# TubeScreamer.net
KiCad netlist of a schematic drawn in EAGLE
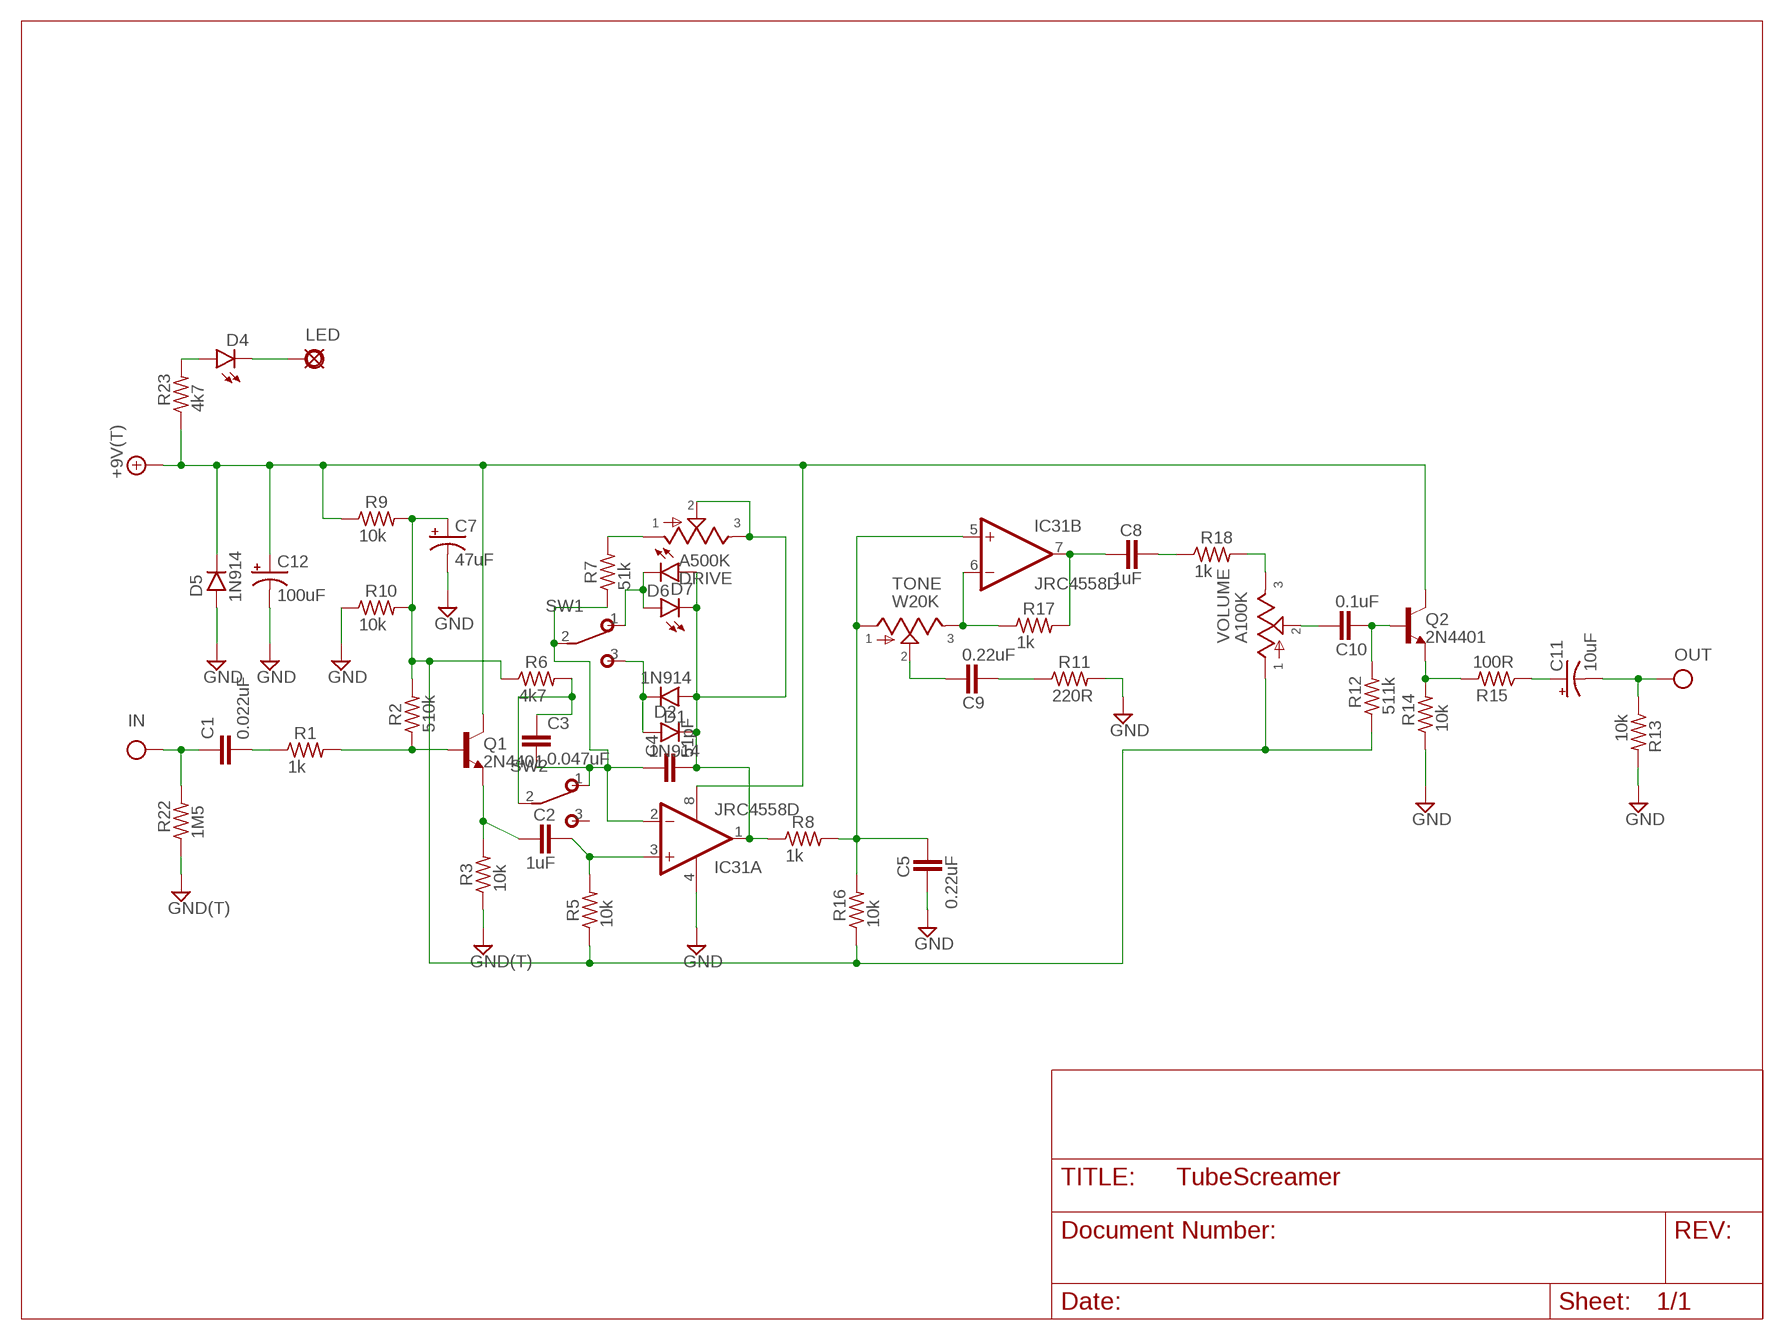
[diagram p0: schematic, sheet 1]

(export (version "E")
  (design (tool "Eeschema 10.0.6"))
  (components
    (comp (ref "+9V")
      (value "+9V(T)")
      (footprint "eagle-import:SQUARE")
      (libsource (lib "eagle-import") (part "+9V(T)"))
    )
    (comp (ref "C1")
      (value "0.022uF")
      (footprint "eagle-import:070X030")
      (libsource (lib "eagle-import") (part "070X0302"))
    )
    (comp (ref "C2")
      (value "1uF")
      (footprint "eagle-import:072X035")
      (libsource (lib "eagle-import") (part "072X0352"))
    )
    (comp (ref "C3")
      (value "0.047uF")
      (footprint "eagle-import:070X030")
      (libsource (lib "eagle-import") (part "070X0302"))
    )
    (comp (ref "C4")
      (value "51pF")
      (footprint "eagle-import:050X030_025")
      (libsource (lib "eagle-import") (part "050X030_0251"))
    )
    (comp (ref "C5")
      (value "0.22uF")
      (footprint "eagle-import:072X035")
      (libsource (lib "eagle-import") (part "072X0352"))
    )
    (comp (ref "C7")
      (value "47uF")
      (footprint "eagle-import:063_025")
      (libsource (lib "eagle-import") (part "0631"))
    )
    (comp (ref "C8")
      (value "1uF")
      (footprint "eagle-import:072X035")
      (libsource (lib "eagle-import") (part "072X0352"))
    )
    (comp (ref "C9")
      (value "0.22uF")
      (footprint "eagle-import:072X035")
      (libsource (lib "eagle-import") (part "072X0352"))
    )
    (comp (ref "C10")
      (value "0.1uF")
      (footprint "eagle-import:072X035")
      (libsource (lib "eagle-import") (part "072X0352"))
    )
    (comp (ref "C11")
      (value "10uF")
      (footprint "eagle-import:063_025")
      (libsource (lib "eagle-import") (part "0631"))
    )
    (comp (ref "C12")
      (value "100uF")
      (footprint "eagle-import:080_035")
      (libsource (lib "eagle-import") (part "080"))
    )
    (comp (ref "D1")
      (value "1N914")
      (footprint "eagle-import:DO35-3")
      (libsource (lib "eagle-import") (part "1N914.3"))
    )
    (comp (ref "D2")
      (value "1N914")
      (footprint "eagle-import:DO35-3")
      (libsource (lib "eagle-import") (part "1N914.3"))
    )
    (comp (ref "D4")
      (value "LED3MM")
      (footprint "eagle-import:LED3MM")
      (libsource (lib "eagle-import") (part "LED3MM"))
    )
    (comp (ref "D5")
      (value "1N914")
      (footprint "eagle-import:DO35-3")
      (libsource (lib "eagle-import") (part "1N914.3"))
    )
    (comp (ref "D6")
      (value "LED3MM")
      (footprint "eagle-import:LED3MM")
      (libsource (lib "eagle-import") (part "LED3MM"))
    )
    (comp (ref "D7")
      (value "LED3MM")
      (footprint "eagle-import:LED3MM")
      (libsource (lib "eagle-import") (part "LED3MM"))
    )
    (comp (ref "DRIVE")
      (value "A500K")
      (footprint "eagle-import:16MM")
      (libsource (lib "eagle-import") (part "POT16MM"))
    )
    (comp (ref "GD2")
      (value "GND(T)")
      (footprint "eagle-import:SQUARE")
      (libsource (lib "eagle-import") (part "GND(T)"))
    )
    (comp (ref "GND")
      (value "GND(T)")
      (footprint "eagle-import:SQUARE")
      (libsource (lib "eagle-import") (part "GND(T)"))
    )
    (comp (ref "IC31")
      (value "JRC4558D")
      (footprint "eagle-import:DIL08")
      (libsource (lib "eagle-import") (part "4558NLM"))
    )
    (comp (ref "IN")
      (value "IN(T)")
      (footprint "eagle-import:SQUARE")
      (libsource (lib "eagle-import") (part "IN(T)"))
    )
    (comp (ref "LED")
      (value "3mm")
      (footprint "eagle-import:SQUARE")
      (libsource (lib "eagle-import") (part "PAD"))
    )
    (comp (ref "OUT")
      (value "OUT(T)")
      (footprint "eagle-import:SQUARE")
      (libsource (lib "eagle-import") (part "OUT(T)"))
    )
    (comp (ref "Q1")
      (value "2N4401")
      (footprint "eagle-import:TO92-")
      (libsource (lib "eagle-import") (part "2N3904"))
    )
    (comp (ref "Q2")
      (value "2N4401")
      (footprint "eagle-import:TO92-")
      (libsource (lib "eagle-import") (part "2N3904"))
    )
    (comp (ref "R1")
      (value "1k")
      (footprint "eagle-import:R0207_3")
      (libsource (lib "eagle-import") (part "6MM.3"))
    )
    (comp (ref "R2")
      (value "510k")
      (footprint "eagle-import:R0207_3")
      (libsource (lib "eagle-import") (part "6MM.3"))
    )
    (comp (ref "R3")
      (value "10k")
      (footprint "eagle-import:R0207_3")
      (libsource (lib "eagle-import") (part "6MM.3"))
    )
    (comp (ref "R5")
      (value "10k")
      (footprint "eagle-import:R0207_3")
      (libsource (lib "eagle-import") (part "6MM.3"))
    )
    (comp (ref "R6")
      (value "4k7")
      (footprint "eagle-import:R0207_3")
      (libsource (lib "eagle-import") (part "6MM.3"))
    )
    (comp (ref "R7")
      (value "51k")
      (footprint "eagle-import:R0207_3")
      (libsource (lib "eagle-import") (part "6MM.3"))
    )
    (comp (ref "R8")
      (value "1k")
      (footprint "eagle-import:R0207_3")
      (libsource (lib "eagle-import") (part "6MM.3"))
    )
    (comp (ref "R9")
      (value "10k")
      (footprint "eagle-import:R0207_3")
      (libsource (lib "eagle-import") (part "6MM.3"))
    )
    (comp (ref "R10")
      (value "10k")
      (footprint "eagle-import:R0207_3")
      (libsource (lib "eagle-import") (part "6MM.3"))
    )
    (comp (ref "R11")
      (value "220R")
      (footprint "eagle-import:R0207_3")
      (libsource (lib "eagle-import") (part "6MM.3"))
    )
    (comp (ref "R12")
      (value "511k")
      (footprint "eagle-import:R0207_3")
      (libsource (lib "eagle-import") (part "6MM.3"))
    )
    (comp (ref "R13")
      (value "10k")
      (footprint "eagle-import:R0207_3")
      (libsource (lib "eagle-import") (part "6MM.3"))
    )
    (comp (ref "R14")
      (value "10k")
      (footprint "eagle-import:R0207_3")
      (libsource (lib "eagle-import") (part "6MM.3"))
    )
    (comp (ref "R15")
      (value "100R")
      (footprint "eagle-import:R0207_3")
      (libsource (lib "eagle-import") (part "6MM.3"))
    )
    (comp (ref "R16")
      (value "10k")
      (footprint "eagle-import:R0207_3")
      (libsource (lib "eagle-import") (part "6MM.3"))
    )
    (comp (ref "R17")
      (value "1k")
      (footprint "eagle-import:R0207_3")
      (libsource (lib "eagle-import") (part "6MM.3"))
    )
    (comp (ref "R18")
      (value "1k")
      (footprint "eagle-import:R0207_3")
      (libsource (lib "eagle-import") (part "6MM.3"))
    )
    (comp (ref "R22")
      (value "1M5")
      (footprint "eagle-import:R0207_3")
      (libsource (lib "eagle-import") (part "6MM.3"))
    )
    (comp (ref "R23")
      (value "4k7")
      (footprint "eagle-import:R0207_3")
      (libsource (lib "eagle-import") (part "6MM.3"))
    )
    (comp (ref "SW1")
      (value "DIODES")
      (footprint "eagle-import:M9040P")
      (libsource (lib "eagle-import") (part "SPDT"))
    )
    (comp (ref "SW2")
      (value "FAT")
      (footprint "eagle-import:M9040P")
      (libsource (lib "eagle-import") (part "SPDT"))
    )
    (comp (ref "TONE")
      (value "W20K")
      (footprint "eagle-import:16MM")
      (libsource (lib "eagle-import") (part "POT16MM"))
    )
    (comp (ref "VOLUME")
      (value "A100K")
      (footprint "eagle-import:16MM")
      (libsource (lib "eagle-import") (part "POT16MM"))
    )
  )
  (nets
    (net (code "1") (name "+9V(T)") (class "Default")
      (node (ref "+9V") (pin "1") (pinfunction "+9V_1") (pintype "power_in"))
      (node (ref "C12") (pin "+") (pinfunction "+_+") (pintype "passive"))
      (node (ref "D5") (pin "C") (pinfunction "C_C") (pintype "passive"))
      (node (ref "IC31") (pin "8") (pinfunction "V+_8") (pintype "power_in"))
      (node (ref "Q1") (pin "1") (pinfunction "C_1") (pintype "passive"))
      (node (ref "Q2") (pin "1") (pinfunction "C_1") (pintype "passive"))
      (node (ref "R23") (pin "1") (pinfunction "1_1") (pintype "passive"))
      (node (ref "R9") (pin "1") (pinfunction "1_1") (pintype "passive"))
    )
    (net (code "2") (name "GND") (class "Default")
      (node (ref "C12") (pin "-") (pinfunction "-_-") (pintype "passive"))
      (node (ref "C5") (pin "1") (pinfunction "1_1") (pintype "passive"))
      (node (ref "C7") (pin "-") (pinfunction "-_-") (pintype "passive"))
      (node (ref "D5") (pin "A") (pinfunction "A_A") (pintype "passive"))
      (node (ref "GD2") (pin "1") (pinfunction "GND_1") (pintype "power_in"))
      (node (ref "GND") (pin "1") (pinfunction "GND_1") (pintype "power_in"))
      (node (ref "IC31") (pin "4") (pinfunction "V-_4") (pintype "power_in"))
      (node (ref "R10") (pin "1") (pinfunction "1_1") (pintype "passive"))
      (node (ref "R11") (pin "2") (pinfunction "2_2") (pintype "passive"))
      (node (ref "R13") (pin "2") (pinfunction "2_2") (pintype "passive"))
      (node (ref "R14") (pin "1") (pinfunction "1_1") (pintype "passive"))
      (node (ref "R22") (pin "1") (pinfunction "1_1") (pintype "passive"))
      (node (ref "R3") (pin "1") (pinfunction "1_1") (pintype "passive"))
    )
    (net (code "3") (name "IN(T)") (class "Default")
      (node (ref "C1") (pin "1") (pinfunction "1_1") (pintype "passive"))
      (node (ref "IN") (pin "1") (pinfunction "IN_1") (pintype "power_in"))
      (node (ref "R22") (pin "2") (pinfunction "2_2") (pintype "passive"))
    )
    (net (code "4") (name "Net-(C1-Pad2)") (class "Default")
      (node (ref "C1") (pin "2") (pinfunction "2_2") (pintype "passive"))
      (node (ref "R1") (pin "1") (pinfunction "1_1") (pintype "passive"))
    )
    (net (code "5") (name "Net-(C7-Pad+)") (class "Default")
      (node (ref "C7") (pin "+") (pinfunction "+_+") (pintype "passive"))
      (node (ref "R10") (pin "2") (pinfunction "2_2") (pintype "passive"))
      (node (ref "R12") (pin "1") (pinfunction "1_1") (pintype "passive"))
      (node (ref "R16") (pin "1") (pinfunction "1_1") (pintype "passive"))
      (node (ref "R2") (pin "2") (pinfunction "2_2") (pintype "passive"))
      (node (ref "R5") (pin "1") (pinfunction "1_1") (pintype "passive"))
      (node (ref "R6") (pin "1") (pinfunction "1_1") (pintype "passive"))
      (node (ref "R9") (pin "2") (pinfunction "2_2") (pintype "passive"))
      (node (ref "VOLUME") (pin "1") (pinfunction "1_1") (pintype "passive"))
    )
    (net (code "6") (name "Net-(C8-Pad2)") (class "Default")
      (node (ref "C8") (pin "2") (pinfunction "2_2") (pintype "passive"))
      (node (ref "R18") (pin "1") (pinfunction "1_1") (pintype "passive"))
    )
    (net (code "7") (name "Net-(C9-Pad1)") (class "Default")
      (node (ref "C9") (pin "1") (pinfunction "1_1") (pintype "passive"))
      (node (ref "R11") (pin "1") (pinfunction "1_1") (pintype "passive"))
    )
    (net (code "8") (name "Net-(C9-Pad2)") (class "Default")
      (node (ref "C9") (pin "2") (pinfunction "2_2") (pintype "passive"))
      (node (ref "TONE") (pin "2") (pinfunction "2_2") (pintype "passive"))
    )
    (net (code "9") (name "Net-(C10-Pad2)") (class "Default")
      (node (ref "C10") (pin "2") (pinfunction "2_2") (pintype "passive"))
      (node (ref "VOLUME") (pin "2") (pinfunction "2_2") (pintype "passive"))
    )
    (net (code "10") (name "Net-(C11-Pad+)") (class "Default")
      (node (ref "C11") (pin "+") (pinfunction "+_+") (pintype "passive"))
      (node (ref "R15") (pin "1") (pinfunction "1_1") (pintype "passive"))
    )
    (net (code "11") (name "Net-(D4-C)") (class "Default")
      (node (ref "D4") (pin "K") (pinfunction "C_K") (pintype "passive"))
      (node (ref "LED") (pin "1") (pinfunction "PAD_1") (pintype "passive"))
    )
    (net (code "12") (name "Net-(D4-PadA)") (class "Default")
      (node (ref "D4") (pin "A") (pinfunction "A_A") (pintype "passive"))
      (node (ref "R23") (pin "2") (pinfunction "2_2") (pintype "passive"))
    )
    (net (code "13") (name "Net-(D6-C)") (class "Default")
      (node (ref "D6") (pin "K") (pinfunction "C_K") (pintype "passive"))
      (node (ref "D7") (pin "A") (pinfunction "A_A") (pintype "passive"))
      (node (ref "SW1") (pin "1") (pinfunction "O_1") (pintype "passive"))
    )
    (net (code "14") (name "Net-(D7-C)") (class "Default")
      (node (ref "C4") (pin "2") (pinfunction "2_2") (pintype "passive"))
      (node (ref "D1") (pin "A") (pinfunction "A_A") (pintype "passive"))
      (node (ref "D2") (pin "C") (pinfunction "C_C") (pintype "passive"))
      (node (ref "D6") (pin "A") (pinfunction "A_A") (pintype "passive"))
      (node (ref "D7") (pin "K") (pinfunction "C_K") (pintype "passive"))
      (node (ref "DRIVE") (pin "2") (pinfunction "2_2") (pintype "passive"))
      (node (ref "DRIVE") (pin "3") (pinfunction "3_3") (pintype "passive"))
      (node (ref "IC31") (pin "1") (pinfunction "OUT_1") (pintype "output"))
      (node (ref "R8") (pin "1") (pinfunction "1_1") (pintype "passive"))
    )
    (net (code "15") (name "Net-(DRIVE-Pad1)") (class "Default")
      (node (ref "DRIVE") (pin "1") (pinfunction "1_1") (pintype "passive"))
      (node (ref "R7") (pin "2") (pinfunction "2_2") (pintype "passive"))
    )
    (net (code "16") (name "Net-(IC31A-+IN)") (class "Default")
      (node (ref "C2") (pin "2") (pinfunction "2_2") (pintype "passive"))
      (node (ref "IC31") (pin "3") (pinfunction "+IN_3") (pintype "input"))
      (node (ref "R5") (pin "2") (pinfunction "2_2") (pintype "passive"))
    )
    (net (code "17") (name "Net-(IC31A--IN)") (class "Default")
      (node (ref "C3") (pin "2") (pinfunction "2_2") (pintype "passive"))
      (node (ref "C4") (pin "1") (pinfunction "1_1") (pintype "passive"))
      (node (ref "IC31") (pin "2") (pinfunction "-IN_2") (pintype "input"))
      (node (ref "R7") (pin "1") (pinfunction "1_1") (pintype "passive"))
      (node (ref "SW1") (pin "2") (pinfunction "P_2") (pintype "passive"))
      (node (ref "SW2") (pin "1") (pinfunction "O_1") (pintype "passive"))
    )
    (net (code "18") (name "Net-(IC31B-+IN)") (class "Default")
      (node (ref "C5") (pin "2") (pinfunction "2_2") (pintype "passive"))
      (node (ref "IC31") (pin "5") (pinfunction "+IN_5") (pintype "input"))
      (node (ref "R16") (pin "2") (pinfunction "2_2") (pintype "passive"))
      (node (ref "R8") (pin "2") (pinfunction "2_2") (pintype "passive"))
      (node (ref "TONE") (pin "1") (pinfunction "1_1") (pintype "passive"))
    )
    (net (code "19") (name "Net-(IC31B--IN)") (class "Default")
      (node (ref "IC31") (pin "6") (pinfunction "-IN_6") (pintype "input"))
      (node (ref "R17") (pin "1") (pinfunction "1_1") (pintype "passive"))
      (node (ref "TONE") (pin "3") (pinfunction "3_3") (pintype "passive"))
    )
    (net (code "20") (name "Net-(IC31B-OUT)") (class "Default")
      (node (ref "C8") (pin "1") (pinfunction "1_1") (pintype "passive"))
      (node (ref "IC31") (pin "7") (pinfunction "OUT_7") (pintype "output"))
      (node (ref "R17") (pin "2") (pinfunction "2_2") (pintype "passive"))
    )
    (net (code "21") (name "Net-(Q1-B)") (class "Default")
      (node (ref "Q1") (pin "2") (pinfunction "B_2") (pintype "passive"))
      (node (ref "R1") (pin "2") (pinfunction "2_2") (pintype "passive"))
      (node (ref "R2") (pin "1") (pinfunction "1_1") (pintype "passive"))
    )
    (net (code "22") (name "Net-(Q1-E)") (class "Default")
      (node (ref "C2") (pin "1") (pinfunction "1_1") (pintype "passive"))
      (node (ref "Q1") (pin "3") (pinfunction "E_3") (pintype "passive"))
      (node (ref "R3") (pin "2") (pinfunction "2_2") (pintype "passive"))
    )
    (net (code "23") (name "Net-(Q2-B)") (class "Default")
      (node (ref "C10") (pin "1") (pinfunction "1_1") (pintype "passive"))
      (node (ref "Q2") (pin "2") (pinfunction "B_2") (pintype "passive"))
      (node (ref "R12") (pin "2") (pinfunction "2_2") (pintype "passive"))
    )
    (net (code "24") (name "Net-(Q2-E)") (class "Default")
      (node (ref "Q2") (pin "3") (pinfunction "E_3") (pintype "passive"))
      (node (ref "R14") (pin "2") (pinfunction "2_2") (pintype "passive"))
      (node (ref "R15") (pin "2") (pinfunction "2_2") (pintype "passive"))
    )
    (net (code "25") (name "Net-(R18-Pad2)") (class "Default")
      (node (ref "R18") (pin "2") (pinfunction "2_2") (pintype "passive"))
      (node (ref "VOLUME") (pin "3") (pinfunction "3_3") (pintype "passive"))
    )
    (net (code "26") (name "Net-(SW1-S)") (class "Default")
      (node (ref "D1") (pin "C") (pinfunction "C_C") (pintype "passive"))
      (node (ref "D2") (pin "A") (pinfunction "A_A") (pintype "passive"))
      (node (ref "SW1") (pin "3") (pinfunction "S_3") (pintype "passive"))
    )
    (net (code "27") (name "Net-(SW2-P)") (class "Default")
      (node (ref "C3") (pin "1") (pinfunction "1_1") (pintype "passive"))
      (node (ref "R6") (pin "2") (pinfunction "2_2") (pintype "passive"))
      (node (ref "SW2") (pin "2") (pinfunction "P_2") (pintype "passive"))
    )
    (net (code "28") (name "OUT(T)") (class "Default")
      (node (ref "C11") (pin "-") (pinfunction "-_-") (pintype "passive"))
      (node (ref "OUT") (pin "1") (pinfunction "OUT_1") (pintype "power_in"))
      (node (ref "R13") (pin "1") (pinfunction "1_1") (pintype "passive"))
    )
    (net (code "29") (name "unconnected-(SW2-S-Pad3)") (class "Default")
      (node (ref "SW2") (pin "3") (pinfunction "S_3") (pintype "passive"))
    )
  )
)
